# TFT_OLED_Board.net
KiCad netlist of a schematic drawn in Altium Designer
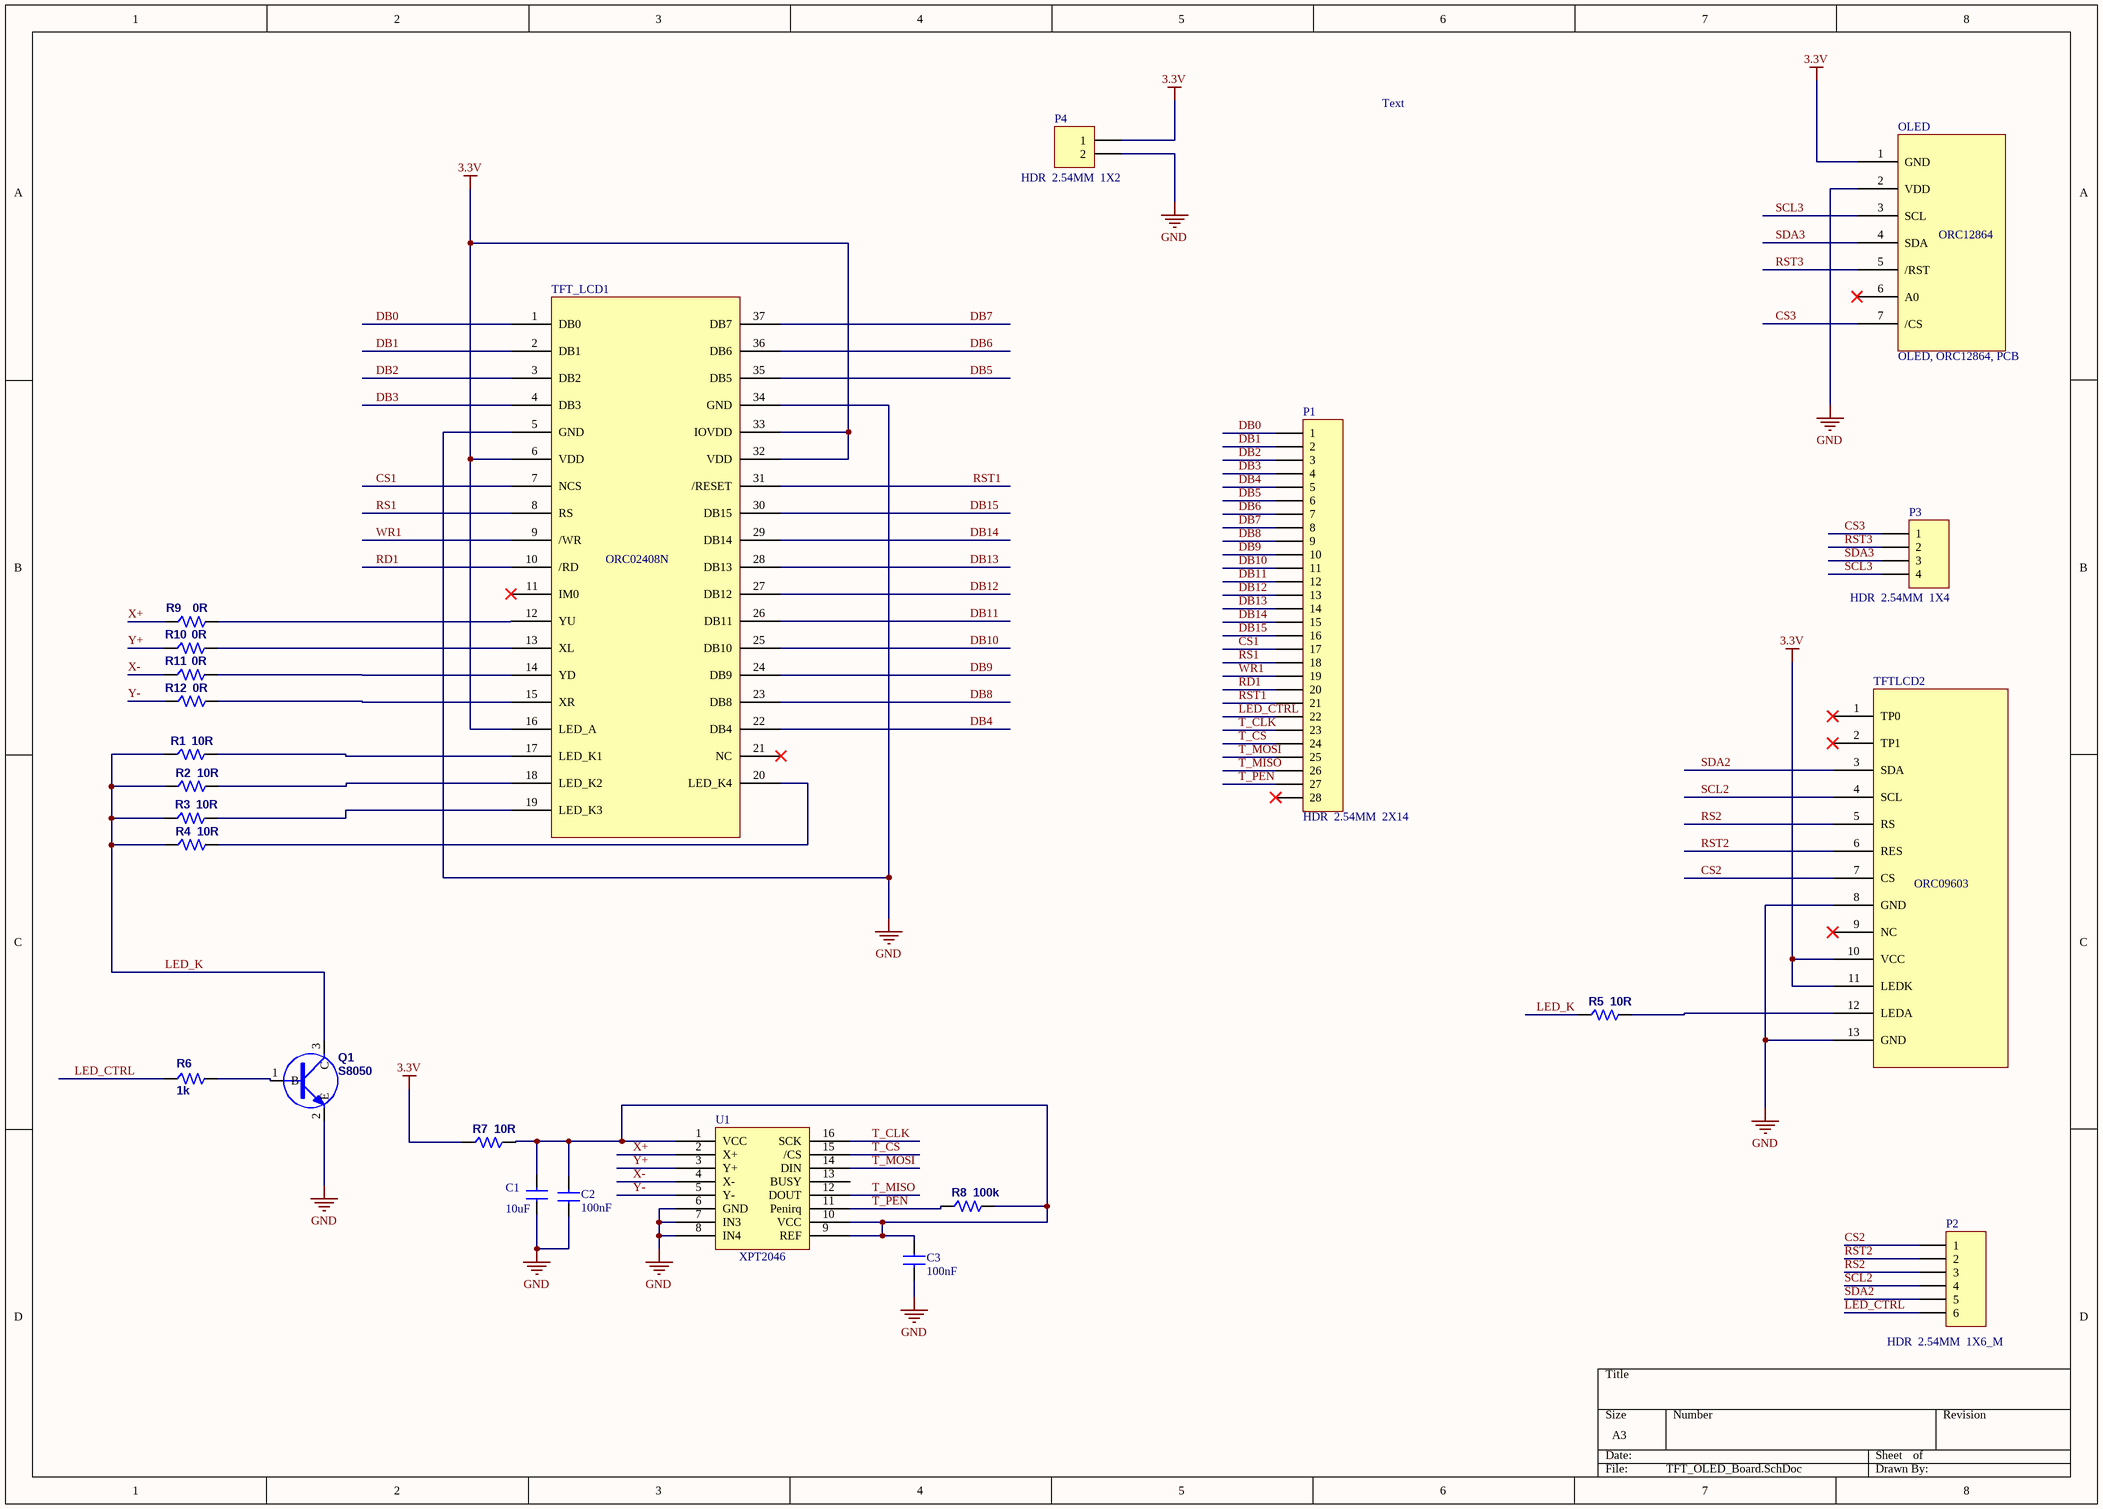
[diagram p0: TFT_OLED_Board.SchDoc]

(export (version "E")
  (design (tool "Eeschema 10.0.6"))
  (components
    (comp (ref "C1")
      (value "10uF")
      (footprint "C0603")
      (description "1206-10UF/50V  106K 贴片层叠电容")
      (libsource (lib "兰格封装") (part "CAP 1206-10uF/50V"))
    )
    (comp (ref "C2")
      (value "100nF")
      (footprint "C0603")
      (description "1206-100nF/50V-J5 104K 贴片层叠电容")
      (libsource (lib "兰格封装") (part "CAP 1206-100nF/50V"))
    )
    (comp (ref "C3")
      (value "100nF")
      (footprint "C1206")
      (description "1206-100nF/50V-J5 104K 贴片层叠电容")
      (libsource (lib "兰格封装") (part "CAP 1206-100nF/50V"))
    )
    (comp (ref "OLED")
      (value "OLED, ORC12864, PCB")
      (footprint "PH2.0  7P")
      (libsource (lib "LCD") (part "OLED_ORC12864"))
    )
    (comp (ref "P1")
      (value "HDR  2.54MM  2X14")
      (footprint "HDR-14X2")
      (libsource (lib "兰格封装") (part "HDR  2.54MM  2X14"))
    )
    (comp (ref "P2")
      (value "HDR  2.54MM  1X6_M")
      (footprint "HDR-1X6_M")
      (libsource (lib "兰格封装") (part "HDR  2.54MM  1X6_M"))
    )
    (comp (ref "P3")
      (value "HDR  2.54MM  1X4")
      (footprint "HDR-1X4")
      (libsource (lib "兰格封装") (part "HDR  2.54MM  1X4"))
    )
    (comp (ref "P4")
      (value "HDR  2.54MM  1X2")
      (footprint "HDR-1x2")
      (libsource (lib "兰格封装") (part "HDR  2.54MM  1X2"))
    )
    (comp (ref "Q1") (value "S8050") (footprint "SOT 23") (libsource (lib "兰格封装") (part "NPN")))
    (comp (ref "R1")
      (value "10R")
      (footprint "R0603")
      (description "0603  0R  5%  贴片电阻")
      (libsource (lib "兰格封装") (part "RES  0603  0R"))
    )
    (comp (ref "R2")
      (value "10R")
      (footprint "R0603")
      (description "0603  0R  5%  贴片电阻")
      (libsource (lib "兰格封装") (part "RES  0603  0R"))
    )
    (comp (ref "R3")
      (value "10R")
      (footprint "R0603")
      (description "0603  0R  5%  贴片电阻")
      (libsource (lib "兰格封装") (part "RES  0603  0R"))
    )
    (comp (ref "R4")
      (value "10R")
      (footprint "R0603")
      (description "0603  0R  5%  贴片电阻")
      (libsource (lib "兰格封装") (part "RES  0603  0R"))
    )
    (comp (ref "R5")
      (value "10R")
      (footprint "R0603")
      (description "0603  0R  5%  贴片电阻")
      (libsource (lib "兰格封装") (part "RES  0603  0R"))
    )
    (comp (ref "R6")
      (value "1k")
      (footprint "R0603")
      (description "0603  0R  5%  贴片电阻")
      (libsource (lib "兰格封装") (part "RES  0603  0R"))
    )
    (comp (ref "R7")
      (value "10R")
      (footprint "R0603")
      (description "0603  0R  5%  贴片电阻")
      (libsource (lib "兰格封装") (part "RES  0603  0R"))
    )
    (comp (ref "R8")
      (value "100k")
      (footprint "R0603")
      (description "0603  0R  5%  贴片电阻")
      (libsource (lib "兰格封装") (part "RES  0603  0R"))
    )
    (comp (ref "R9")
      (value "0R")
      (footprint "R0603")
      (description "0603  0R  5%  贴片电阻")
      (libsource (lib "兰格封装") (part "RES  0603  0R"))
    )
    (comp (ref "R10")
      (value "0R")
      (footprint "R0603")
      (description "0603  0R  5%  贴片电阻")
      (libsource (lib "兰格封装") (part "RES  0603  0R"))
    )
    (comp (ref "R11")
      (value "0R")
      (footprint "R0603")
      (description "0603  0R  5%  贴片电阻")
      (libsource (lib "兰格封装") (part "RES  0603  0R"))
    )
    (comp (ref "R12")
      (value "0R")
      (footprint "R0603")
      (description "0603  0R  5%  贴片电阻")
      (libsource (lib "兰格封装") (part "RES  0603  0R"))
    )
    (comp (ref "TFTLCD2")
      (value "TFT_LCD, ORC09603")
      (footprint "FPC  0.3  13P")
      (libsource (lib "LCD") (part "TFT_ORC09603"))
    )
    (comp (ref "TFT_LCD1")
      (value "TFTLCD, ORC02408N")
      (footprint "FPC  1.0  37P 0.6")
      (libsource (lib "LCD") (part "TFT_ORC02408N"))
    )
    (comp (ref "U1")
      (value "XPT2046")
      (footprint "TSSOP 16")
      (description "HR2046贴片IC")
      (libsource (lib "集成IC") (part "XPT2046"))
    )
  )
  (nets
    (net (code "1") (name "/CS1") (class "Default")
      (node (ref "P1") (pin "17") (pinfunction "17_17") (pintype "passive"))
      (node (ref "TFT_LCD1") (pin "7") (pinfunction "NCS_7") (pintype "passive"))
    )
    (net (code "2") (name "/CS2") (class "Default")
      (node (ref "P2") (pin "1") (pinfunction "1_1") (pintype "passive"))
      (node (ref "TFTLCD2") (pin "7") (pinfunction "CS_7") (pintype "passive"))
    )
    (net (code "3") (name "/CS3") (class "Default")
      (node (ref "OLED") (pin "7") (pinfunction "/CS_7") (pintype "passive"))
      (node (ref "P3") (pin "1") (pinfunction "1_1") (pintype "passive"))
    )
    (net (code "4") (name "/DB0") (class "Default")
      (node (ref "P1") (pin "1") (pinfunction "1_1") (pintype "passive"))
      (node (ref "TFT_LCD1") (pin "1") (pinfunction "DB0_1") (pintype "passive"))
    )
    (net (code "5") (name "/DB1") (class "Default")
      (node (ref "P1") (pin "2") (pinfunction "2_2") (pintype "passive"))
      (node (ref "TFT_LCD1") (pin "2") (pinfunction "DB1_2") (pintype "passive"))
    )
    (net (code "6") (name "/DB2") (class "Default")
      (node (ref "P1") (pin "3") (pinfunction "3_3") (pintype "passive"))
      (node (ref "TFT_LCD1") (pin "3") (pinfunction "DB2_3") (pintype "passive"))
    )
    (net (code "7") (name "/DB3") (class "Default")
      (node (ref "P1") (pin "4") (pinfunction "4_4") (pintype "passive"))
      (node (ref "TFT_LCD1") (pin "4") (pinfunction "DB3_4") (pintype "passive"))
    )
    (net (code "8") (name "/DB4") (class "Default")
      (node (ref "P1") (pin "5") (pinfunction "5_5") (pintype "passive"))
      (node (ref "TFT_LCD1") (pin "22") (pinfunction "DB4_22") (pintype "passive"))
    )
    (net (code "9") (name "/DB5") (class "Default")
      (node (ref "P1") (pin "6") (pinfunction "6_6") (pintype "passive"))
      (node (ref "TFT_LCD1") (pin "35") (pinfunction "DB5_35") (pintype "passive"))
    )
    (net (code "10") (name "/DB6") (class "Default")
      (node (ref "P1") (pin "7") (pinfunction "7_7") (pintype "passive"))
      (node (ref "TFT_LCD1") (pin "36") (pinfunction "DB6_36") (pintype "passive"))
    )
    (net (code "11") (name "/DB7") (class "Default")
      (node (ref "P1") (pin "8") (pinfunction "8_8") (pintype "passive"))
      (node (ref "TFT_LCD1") (pin "37") (pinfunction "DB7_37") (pintype "passive"))
    )
    (net (code "12") (name "/DB8") (class "Default")
      (node (ref "P1") (pin "9") (pinfunction "9_9") (pintype "passive"))
      (node (ref "TFT_LCD1") (pin "23") (pinfunction "DB8_23") (pintype "passive"))
    )
    (net (code "13") (name "/DB9") (class "Default")
      (node (ref "P1") (pin "10") (pinfunction "10_10") (pintype "passive"))
      (node (ref "TFT_LCD1") (pin "24") (pinfunction "DB9_24") (pintype "passive"))
    )
    (net (code "14") (name "/DB10") (class "Default")
      (node (ref "P1") (pin "11") (pinfunction "11_11") (pintype "passive"))
      (node (ref "TFT_LCD1") (pin "25") (pinfunction "DB10_25") (pintype "passive"))
    )
    (net (code "15") (name "/DB11") (class "Default")
      (node (ref "P1") (pin "12") (pinfunction "12_12") (pintype "passive"))
      (node (ref "TFT_LCD1") (pin "26") (pinfunction "DB11_26") (pintype "passive"))
    )
    (net (code "16") (name "/DB12") (class "Default")
      (node (ref "P1") (pin "13") (pinfunction "13_13") (pintype "passive"))
      (node (ref "TFT_LCD1") (pin "27") (pinfunction "DB12_27") (pintype "passive"))
    )
    (net (code "17") (name "/DB13") (class "Default")
      (node (ref "P1") (pin "14") (pinfunction "14_14") (pintype "passive"))
      (node (ref "TFT_LCD1") (pin "28") (pinfunction "DB13_28") (pintype "passive"))
    )
    (net (code "18") (name "/DB14") (class "Default")
      (node (ref "P1") (pin "15") (pinfunction "15_15") (pintype "passive"))
      (node (ref "TFT_LCD1") (pin "29") (pinfunction "DB14_29") (pintype "passive"))
    )
    (net (code "19") (name "/DB15") (class "Default")
      (node (ref "P1") (pin "16") (pinfunction "16_16") (pintype "passive"))
      (node (ref "TFT_LCD1") (pin "30") (pinfunction "DB15_30") (pintype "passive"))
    )
    (net (code "20") (name "/LED_CTRL") (class "Default")
      (node (ref "P1") (pin "22") (pinfunction "22_22") (pintype "passive"))
      (node (ref "P2") (pin "6") (pinfunction "6_6") (pintype "passive"))
      (node (ref "R6") (pin "1") (pintype "passive"))
    )
    (net (code "21") (name "/LED_K") (class "Default")
      (node (ref "Q1") (pin "3") (pinfunction "C_3") (pintype "passive"))
      (node (ref "R1") (pin "1") (pintype "passive"))
      (node (ref "R2") (pin "1") (pintype "passive"))
      (node (ref "R3") (pin "1") (pintype "passive"))
      (node (ref "R4") (pin "1") (pintype "passive"))
      (node (ref "R5") (pin "1") (pintype "passive"))
    )
    (net (code "22") (name "/RD1") (class "Default")
      (node (ref "P1") (pin "20") (pinfunction "20_20") (pintype "passive"))
      (node (ref "TFT_LCD1") (pin "10") (pinfunction "/RD_10") (pintype "passive"))
    )
    (net (code "23") (name "/RS1") (class "Default")
      (node (ref "P1") (pin "18") (pinfunction "18_18") (pintype "passive"))
      (node (ref "TFT_LCD1") (pin "8") (pinfunction "RS_8") (pintype "passive"))
    )
    (net (code "24") (name "/RS2") (class "Default")
      (node (ref "P2") (pin "3") (pinfunction "3_3") (pintype "passive"))
      (node (ref "TFTLCD2") (pin "5") (pinfunction "RS_5") (pintype "passive"))
    )
    (net (code "25") (name "/RST1") (class "Default")
      (node (ref "P1") (pin "21") (pinfunction "21_21") (pintype "passive"))
      (node (ref "TFT_LCD1") (pin "31") (pinfunction "/RESET_31") (pintype "passive"))
    )
    (net (code "26") (name "/RST2") (class "Default")
      (node (ref "P2") (pin "2") (pinfunction "2_2") (pintype "passive"))
      (node (ref "TFTLCD2") (pin "6") (pinfunction "RES_6") (pintype "passive"))
    )
    (net (code "27") (name "/RST3") (class "Default")
      (node (ref "OLED") (pin "5") (pinfunction "/RST_5") (pintype "passive"))
      (node (ref "P3") (pin "2") (pinfunction "2_2") (pintype "passive"))
    )
    (net (code "28") (name "/SCL2") (class "Default")
      (node (ref "P2") (pin "4") (pinfunction "4_4") (pintype "passive"))
      (node (ref "TFTLCD2") (pin "4") (pinfunction "SCL_4") (pintype "passive"))
    )
    (net (code "29") (name "/SCL3") (class "Default")
      (node (ref "OLED") (pin "3") (pinfunction "SCL_3") (pintype "passive"))
      (node (ref "P3") (pin "4") (pinfunction "4_4") (pintype "passive"))
    )
    (net (code "30") (name "/SDA2") (class "Default")
      (node (ref "P2") (pin "5") (pinfunction "5_5") (pintype "passive"))
      (node (ref "TFTLCD2") (pin "3") (pinfunction "SDA_3") (pintype "passive"))
    )
    (net (code "31") (name "/SDA3") (class "Default")
      (node (ref "OLED") (pin "4") (pinfunction "SDA_4") (pintype "passive"))
      (node (ref "P3") (pin "3") (pinfunction "3_3") (pintype "passive"))
    )
    (net (code "32") (name "/T_CLK") (class "Default")
      (node (ref "P1") (pin "23") (pinfunction "23_23") (pintype "passive"))
      (node (ref "U1") (pin "16") (pinfunction "SCK_16") (pintype "passive"))
    )
    (net (code "33") (name "/T_CS") (class "Default")
      (node (ref "P1") (pin "24") (pinfunction "24_24") (pintype "passive"))
      (node (ref "U1") (pin "15") (pinfunction "/CS_15") (pintype "passive"))
    )
    (net (code "34") (name "/T_MISO") (class "Default")
      (node (ref "P1") (pin "26") (pinfunction "26_26") (pintype "passive"))
      (node (ref "U1") (pin "12") (pinfunction "DOUT_12") (pintype "passive"))
    )
    (net (code "35") (name "/T_MOSI") (class "Default")
      (node (ref "P1") (pin "25") (pinfunction "25_25") (pintype "passive"))
      (node (ref "U1") (pin "14") (pinfunction "DIN_14") (pintype "passive"))
    )
    (net (code "36") (name "/T_PEN") (class "Default")
      (node (ref "P1") (pin "27") (pinfunction "27_27") (pintype "passive"))
      (node (ref "R8") (pin "1") (pintype "passive"))
      (node (ref "U1") (pin "11") (pinfunction "Penirq_11") (pintype "passive"))
    )
    (net (code "37") (name "/WR1") (class "Default")
      (node (ref "P1") (pin "19") (pinfunction "19_19") (pintype "passive"))
      (node (ref "TFT_LCD1") (pin "9") (pinfunction "/WR_9") (pintype "passive"))
    )
    (net (code "38") (name "/X+") (class "Default")
      (node (ref "R9") (pin "1") (pintype "passive"))
      (node (ref "U1") (pin "2") (pinfunction "X+_2") (pintype "passive"))
    )
    (net (code "39") (name "/X-") (class "Default")
      (node (ref "R11") (pin "1") (pintype "passive"))
      (node (ref "U1") (pin "4") (pinfunction "X-_4") (pintype "passive"))
    )
    (net (code "40") (name "/Y+") (class "Default")
      (node (ref "R10") (pin "1") (pintype "passive"))
      (node (ref "U1") (pin "3") (pinfunction "Y+_3") (pintype "passive"))
    )
    (net (code "41") (name "/Y-") (class "Default")
      (node (ref "R12") (pin "1") (pintype "passive"))
      (node (ref "U1") (pin "5") (pinfunction "Y-_5") (pintype "passive"))
    )
    (net (code "42") (name "3.3V") (class "Default")
      (node (ref "OLED") (pin "1") (pinfunction "GND_1") (pintype "passive"))
      (node (ref "P4") (pin "1") (pinfunction "1_1") (pintype "passive"))
      (node (ref "R7") (pin "1") (pintype "passive"))
      (node (ref "TFTLCD2") (pin "10") (pinfunction "VCC_10") (pintype "passive"))
      (node (ref "TFTLCD2") (pin "11") (pinfunction "LEDK_11") (pintype "passive"))
      (node (ref "TFT_LCD1") (pin "16") (pinfunction "LED_A_16") (pintype "passive"))
      (node (ref "TFT_LCD1") (pin "32") (pinfunction "VDD_32") (pintype "passive"))
      (node (ref "TFT_LCD1") (pin "33") (pinfunction "IOVDD_33") (pintype "passive"))
      (node (ref "TFT_LCD1") (pin "6") (pinfunction "VDD_6") (pintype "passive"))
    )
    (net (code "43") (name "GND") (class "Default")
      (node (ref "C1") (pin "2") (pinfunction "2_2") (pintype "passive"))
      (node (ref "C2") (pin "2") (pinfunction "2_2") (pintype "passive"))
      (node (ref "C3") (pin "2") (pinfunction "2_2") (pintype "passive"))
      (node (ref "OLED") (pin "2") (pinfunction "VDD_2") (pintype "passive"))
      (node (ref "P4") (pin "2") (pinfunction "2_2") (pintype "passive"))
      (node (ref "Q1") (pin "2") (pinfunction "E_2") (pintype "passive"))
      (node (ref "TFTLCD2") (pin "13") (pinfunction "GND_13") (pintype "passive"))
      (node (ref "TFTLCD2") (pin "8") (pinfunction "GND_8") (pintype "passive"))
      (node (ref "TFT_LCD1") (pin "34") (pinfunction "GND_34") (pintype "passive"))
      (node (ref "TFT_LCD1") (pin "5") (pinfunction "GND_5") (pintype "passive"))
      (node (ref "U1") (pin "6") (pinfunction "GND_6") (pintype "passive"))
      (node (ref "U1") (pin "7") (pinfunction "IN3_7") (pintype "passive"))
      (node (ref "U1") (pin "8") (pinfunction "IN4_8") (pintype "passive"))
    )
    (net (code "44") (name "Net-(Q1-B)") (class "Default")
      (node (ref "Q1") (pin "1") (pinfunction "B_1") (pintype "passive"))
      (node (ref "R6") (pin "2") (pintype "passive"))
    )
    (net (code "45") (name "Net-(TFTLCD2-LEDA)") (class "Default")
      (node (ref "R5") (pin "2") (pintype "passive"))
      (node (ref "TFTLCD2") (pin "12") (pinfunction "LEDA_12") (pintype "passive"))
    )
    (net (code "46") (name "Net-(TFT_LCD1-LED_K1)") (class "Default")
      (node (ref "R1") (pin "2") (pintype "passive"))
      (node (ref "TFT_LCD1") (pin "17") (pinfunction "LED_K1_17") (pintype "passive"))
    )
    (net (code "47") (name "Net-(TFT_LCD1-LED_K2)") (class "Default")
      (node (ref "R2") (pin "2") (pintype "passive"))
      (node (ref "TFT_LCD1") (pin "18") (pinfunction "LED_K2_18") (pintype "passive"))
    )
    (net (code "48") (name "Net-(TFT_LCD1-LED_K3)") (class "Default")
      (node (ref "R3") (pin "2") (pintype "passive"))
      (node (ref "TFT_LCD1") (pin "19") (pinfunction "LED_K3_19") (pintype "passive"))
    )
    (net (code "49") (name "Net-(TFT_LCD1-LED_K4)") (class "Default")
      (node (ref "R4") (pin "2") (pintype "passive"))
      (node (ref "TFT_LCD1") (pin "20") (pinfunction "LED_K4_20") (pintype "passive"))
    )
    (net (code "50") (name "Net-(TFT_LCD1-XL)") (class "Default")
      (node (ref "R10") (pin "2") (pintype "passive"))
      (node (ref "TFT_LCD1") (pin "13") (pinfunction "XL_13") (pintype "passive"))
    )
    (net (code "51") (name "Net-(TFT_LCD1-XR)") (class "Default")
      (node (ref "R12") (pin "2") (pintype "passive"))
      (node (ref "TFT_LCD1") (pin "15") (pinfunction "XR_15") (pintype "passive"))
    )
    (net (code "52") (name "Net-(TFT_LCD1-YD)") (class "Default")
      (node (ref "R11") (pin "2") (pintype "passive"))
      (node (ref "TFT_LCD1") (pin "14") (pinfunction "YD_14") (pintype "passive"))
    )
    (net (code "53") (name "Net-(TFT_LCD1-YU)") (class "Default")
      (node (ref "R9") (pin "2") (pintype "passive"))
      (node (ref "TFT_LCD1") (pin "12") (pinfunction "YU_12") (pintype "passive"))
    )
    (net (code "54") (name "Net-(U1-REF)") (class "Default")
      (node (ref "C1") (pin "1") (pinfunction "1_1") (pintype "passive"))
      (node (ref "C2") (pin "1") (pinfunction "1_1") (pintype "passive"))
      (node (ref "C3") (pin "1") (pinfunction "1_1") (pintype "passive"))
      (node (ref "R7") (pin "2") (pintype "passive"))
      (node (ref "R8") (pin "2") (pintype "passive"))
      (node (ref "U1") (pin "1") (pinfunction "VCC_1") (pintype "passive"))
      (node (ref "U1") (pin "10") (pinfunction "VCC_10") (pintype "passive"))
      (node (ref "U1") (pin "9") (pinfunction "REF_9") (pintype "passive"))
    )
    (net (code "55") (name "unconnected-(OLED-A0-Pad6)") (class "Default")
      (node (ref "OLED") (pin "6") (pinfunction "A0_6") (pintype "passive+no_connect"))
    )
    (net (code "56") (name "unconnected-(P1-Pad28)") (class "Default")
      (node (ref "P1") (pin "28") (pinfunction "28_28") (pintype "passive+no_connect"))
    )
    (net (code "57") (name "unconnected-(TFTLCD2-NC-Pad9)") (class "Default")
      (node (ref "TFTLCD2") (pin "9") (pinfunction "NC_9") (pintype "passive+no_connect"))
    )
    (net (code "58") (name "unconnected-(TFTLCD2-TP0-Pad1)") (class "Default")
      (node (ref "TFTLCD2") (pin "1") (pinfunction "TP0_1") (pintype "passive+no_connect"))
    )
    (net (code "59") (name "unconnected-(TFTLCD2-TP1-Pad2)") (class "Default")
      (node (ref "TFTLCD2") (pin "2") (pinfunction "TP1_2") (pintype "passive+no_connect"))
    )
    (net (code "60") (name "unconnected-(TFT_LCD1-IM0-Pad11)") (class "Default")
      (node (ref "TFT_LCD1") (pin "11") (pinfunction "IM0_11") (pintype "passive+no_connect"))
    )
    (net (code "61") (name "unconnected-(TFT_LCD1-NC-Pad21)") (class "Default")
      (node (ref "TFT_LCD1") (pin "21") (pinfunction "NC_21") (pintype "passive+no_connect"))
    )
    (net (code "62") (name "unconnected-(U1-BUSY-Pad13)") (class "Default")
      (node (ref "U1") (pin "13") (pinfunction "BUSY_13") (pintype "passive"))
    )
  )
)
